# USB.net
KiCad netlist of a schematic drawn in Altium Designer
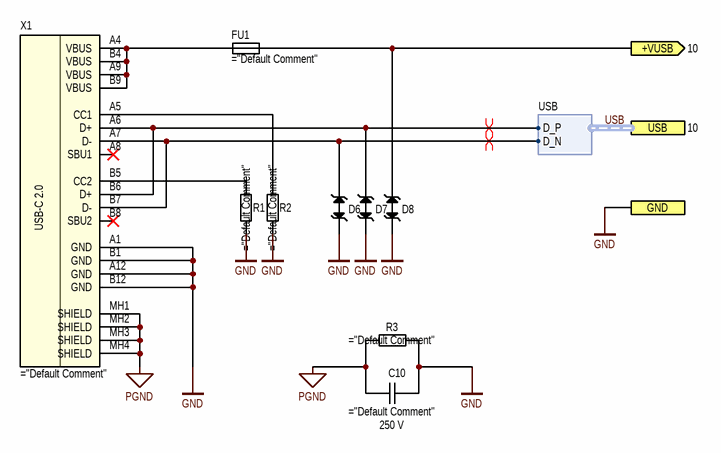
[diagram p0: USB.SchDoc]

(export (version "E")
  (design (tool "Eeschema 10.0.6"))
  (components
    (comp (ref "C10")
      (value "~")
      (description "CAP CER 4700PF 250V X7R 0805")
      (fields
        (field (name "TOLERANCE") "10 %")
        (field (name "MANUFACTURER") "YAGEO")
        (field (name "RATED VOLTAGE") "250 V")
      )
      (libsource (lib "femtoino") (part "CC0805KRX7RYBB472"))
    )
    (comp (ref "D6")
      (value "~")
      (description "TVS DIODE 5VWM 20VC SOD882")
      (fields (field (name "TOLERANCE") "* %") (field (name "MANUFACTURER") "YAGEO"))
      (libsource (lib "femtoino") (part "UAD8C05L01"))
    )
    (comp (ref "D7")
      (value "~")
      (description "TVS DIODE 5VWM 20VC SOD882")
      (fields (field (name "TOLERANCE") "* %") (field (name "MANUFACTURER") "YAGEO"))
      (libsource (lib "femtoino") (part "UAD8C05L01"))
    )
    (comp (ref "D8")
      (value "~")
      (description "TVS DIODE 5VWM 20VC SOD882")
      (fields (field (name "TOLERANCE") "* %") (field (name "MANUFACTURER") "YAGEO"))
      (libsource (lib "femtoino") (part "UAD8C05L01"))
    )
    (comp (ref "FU1")
      (value "~")
      (description "FUSE 500MA 5V FAST 0603 SMD")
      (fields (field (name "TOLERANCE") "* %") (field (name "MANUFACTURER") "Littelfuse Inc."))
      (libsource (lib "femtoino") (part "04000025WR"))
    )
    (comp (ref "R1")
      (value "~")
      (description "RES 5.1K OHM 1% 1/10W 0603")
      (fields (field (name "TOLERANCE") "1 %") (field (name "MANUFACTURER") "YAGEO"))
      (libsource (lib "femtoino") (part "RC0603FR-075K1L"))
    )
    (comp (ref "R2")
      (value "~")
      (description "RES 5.1K OHM 1% 1/10W 0603")
      (fields (field (name "TOLERANCE") "1 %") (field (name "MANUFACTURER") "YAGEO"))
      (libsource (lib "femtoino") (part "RC0603FR-075K1L"))
    )
    (comp (ref "R3")
      (value "~")
      (description "RES 1M OHM 1% 1/10W 0603")
      (fields (field (name "TOLERANCE") "1 %") (field (name "MANUFACTURER") "YAGEO"))
      (libsource (lib "femtoino") (part "RC0603FR-071ML"))
    )
    (comp (ref "X1")
      (value "~")
      (description "CONN RCPT USB2.0 TYPE C 16+8POS")
      (fields (field (name "TOLERANCE") "* %") (field (name "MANUFACTURER") "GCT"))
      (libsource (lib "femtoino") (part "USB4085-GF-A"))
    )
  )
  (nets
    (net (code "2") (name "/+VUSB") (class "Default")
      (node (ref "D8") (pin "1") (pinfunction "1_1") (pintype "passive"))
      (node (ref "FU1") (pin "2") (pinfunction "2_2") (pintype "passive"))
    )
    (net (code "4") (name "GND") (class "Default")
      (node (ref "C10") (pin "2") (pinfunction "2_2") (pintype "passive"))
      (node (ref "D6") (pin "2") (pinfunction "2_2") (pintype "passive"))
      (node (ref "D7") (pin "2") (pinfunction "2_2") (pintype "passive"))
      (node (ref "D8") (pin "2") (pinfunction "2_2") (pintype "passive"))
      (node (ref "R1") (pin "2") (pinfunction "2_2") (pintype "passive"))
      (node (ref "R2") (pin "2") (pinfunction "2_2") (pintype "passive"))
      (node (ref "R3") (pin "2") (pinfunction "2_2") (pintype "passive"))
      (node (ref "X1") (pin "A1") (pinfunction "GND_A1") (pintype "passive"))
      (node (ref "X1") (pin "A12") (pinfunction "GND_A12") (pintype "passive"))
      (node (ref "X1") (pin "B1") (pinfunction "GND_B1") (pintype "passive"))
      (node (ref "X1") (pin "B12") (pinfunction "GND_B12") (pintype "passive"))
    )
    (net (code "5") (name "Net-(D6-Pad1)") (class "Default")
      (node (ref "D6") (pin "1") (pinfunction "1_1") (pintype "passive"))
      (node (ref "X1") (pin "A7") (pinfunction "D-_A7") (pintype "passive"))
      (node (ref "X1") (pin "B7") (pinfunction "D-_B7") (pintype "passive"))
    )
    (net (code "6") (name "Net-(D7-Pad1)") (class "Default")
      (node (ref "D7") (pin "1") (pinfunction "1_1") (pintype "passive"))
      (node (ref "X1") (pin "A6") (pinfunction "D+_A6") (pintype "passive"))
      (node (ref "X1") (pin "B6") (pinfunction "D+_B6") (pintype "passive"))
    )
    (net (code "7") (name "Net-(FU1-Pad1)") (class "Default")
      (node (ref "FU1") (pin "1") (pinfunction "1_1") (pintype "passive"))
      (node (ref "X1") (pin "A4") (pinfunction "VBUS_A4") (pintype "passive"))
      (node (ref "X1") (pin "A9") (pinfunction "VBUS_A9") (pintype "passive"))
      (node (ref "X1") (pin "B4") (pinfunction "VBUS_B4") (pintype "passive"))
      (node (ref "X1") (pin "B9") (pinfunction "VBUS_B9") (pintype "passive"))
    )
    (net (code "8") (name "Net-(X1-CC1)") (class "Default")
      (node (ref "R2") (pin "1") (pinfunction "1_1") (pintype "passive"))
      (node (ref "X1") (pin "A5") (pinfunction "CC1_A5") (pintype "passive"))
    )
    (net (code "9") (name "Net-(X1-CC2)") (class "Default")
      (node (ref "R1") (pin "1") (pinfunction "1_1") (pintype "passive"))
      (node (ref "X1") (pin "B5") (pinfunction "CC2_B5") (pintype "passive"))
    )
    (net (code "10") (name "PGND") (class "Default")
      (node (ref "C10") (pin "1") (pinfunction "1_1") (pintype "passive"))
      (node (ref "R3") (pin "1") (pinfunction "1_1") (pintype "passive"))
      (node (ref "X1") (pin "MH1") (pinfunction "SHIELD_MH1") (pintype "passive"))
      (node (ref "X1") (pin "MH2") (pinfunction "SHIELD_MH2") (pintype "passive"))
      (node (ref "X1") (pin "MH3") (pinfunction "SHIELD_MH3") (pintype "passive"))
      (node (ref "X1") (pin "MH4") (pinfunction "SHIELD_MH4") (pintype "passive"))
    )
    (net (code "11") (name "unconnected-(X1-SBU1-PadA8)") (class "Default")
      (node (ref "X1") (pin "A8") (pinfunction "SBU1_A8") (pintype "passive+no_connect"))
    )
    (net (code "12") (name "unconnected-(X1-SBU2-PadB8)") (class "Default")
      (node (ref "X1") (pin "B8") (pinfunction "SBU2_B8") (pintype "passive+no_connect"))
    )
  )
)
